# Sensor.net
KiCad netlist of a schematic drawn in Altium Designer
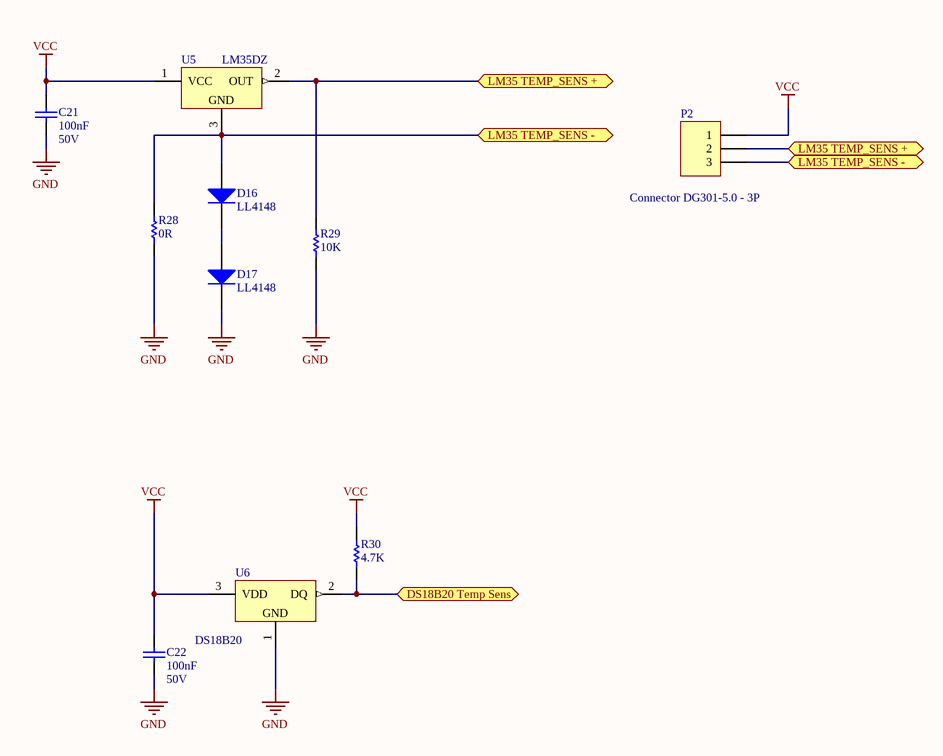
[diagram p0: Sensor.SchDoc]

(export (version "E")
  (design (tool "Eeschema 10.0.6"))
  (components
    (comp (ref "C21")
      (value "100nF")
      (footprint "3-0603_L")
      (description "Capacitor")
      (fields
        (field (name "VOLTAGE") "50V")
        (field (name "Comment") "Cap")
        (field (name "PUBLISHER") "Altium Limited")
      )
      (libsource (lib "Erdem_05112012") (part "Cap"))
    )
    (comp (ref "C22")
      (value "100nF")
      (footprint "3-0603_L")
      (description "Capacitor")
      (fields
        (field (name "VOLTAGE") "50V")
        (field (name "Comment") "Cap")
        (field (name "PUBLISHER") "Altium Limited")
      )
      (libsource (lib "Erdem_05112012") (part "Cap"))
    )
    (comp (ref "D16")
      (value "LL4148")
      (footprint "DL-35 - S")
      (description "1 Amp General Purpose Rectifier")
      (fields (field (name "PUBLISHER") "Altium Limited"))
      (libsource (lib "Erdem_05112012") (part "LL4148"))
    )
    (comp (ref "D17")
      (value "LL4148")
      (footprint "DL-35 - S")
      (description "1 Amp General Purpose Rectifier")
      (fields (field (name "PUBLISHER") "Altium Limited"))
      (libsource (lib "Erdem_05112012") (part "LL4148"))
    )
    (comp (ref "P2")
      (value "Connector DG301-5.0 - 3P")
      (footprint "Connector DG301-5.0 - 3P")
      (description "Connector, 3-Pin")
      (fields (field (name "PUBLISHER") "Altium Limited"))
      (libsource (lib "Erdem_05112012") (part "Connector DG301-5.0 - 3P"))
    )
    (comp (ref "R28")
      (value "0R")
      (footprint "8-1206")
      (description "Resistor")
      (fields (field (name "Comment") "Res1") (field (name "PUBLISHER") "Altium Limited"))
      (libsource (lib "Erdem_05112012") (part "Res1"))
    )
    (comp (ref "R29")
      (value "10K")
      (footprint "3-0603_L")
      (description "Resistor")
      (fields (field (name "Comment") "Res1") (field (name "PUBLISHER") "Altium Limited"))
      (libsource (lib "Erdem_05112012") (part "Res1"))
    )
    (comp (ref "R30")
      (value "4.7K")
      (footprint "3-0603_L")
      (description "Resistor")
      (fields (field (name "Comment") "Res1") (field (name "PUBLISHER") "Altium Limited"))
      (libsource (lib "Erdem_05112012") (part "Res1"))
    )
    (comp (ref "U5")
      (value "LM35DZ")
      (footprint "TO-92 Big")
      (description "Temperature Sensor")
      (fields (field (name "PUBLISHER") "Altium Limited"))
      (libsource (lib "Erdem_05112012") (part "LM35DZ"))
    )
    (comp (ref "U6")
      (value "DS18B20")
      (footprint "TO-92 Big")
      (description "1-Wire Temperature Sensor")
      (fields (field (name "PUBLISHER") "Altium Limited"))
      (libsource (lib "Erdem_05112012") (part "DS18B20"))
    )
  )
  (nets
    (net (code "1") (name "/DS18B20 Temp Sens") (class "Default")
      (node (ref "R30") (pin "1") (pinfunction "1_1") (pintype "passive"))
      (node (ref "U6") (pin "2") (pinfunction "DQ_2") (pintype "output"))
    )
    (net (code "2") (name "/LM35 TEMP_SENS +") (class "Default")
      (node (ref "P2") (pin "2") (pinfunction "2_2") (pintype "passive"))
      (node (ref "R29") (pin "2") (pinfunction "2_2") (pintype "passive"))
      (node (ref "U5") (pin "2") (pinfunction "OUT_2") (pintype "output"))
    )
    (net (code "3") (name "/LM35 TEMP_SENS -") (class "Default")
      (node (ref "D16") (pin "1") (pinfunction "A_1") (pintype "passive"))
      (node (ref "P2") (pin "3") (pinfunction "3_3") (pintype "passive"))
      (node (ref "R28") (pin "2") (pinfunction "2_2") (pintype "passive"))
      (node (ref "U5") (pin "3") (pinfunction "GND_3") (pintype "power_in"))
    )
    (net (code "4") (name "GND") (class "Default")
      (node (ref "C21") (pin "1") (pinfunction "1_1") (pintype "passive"))
      (node (ref "C22") (pin "1") (pinfunction "1_1") (pintype "passive"))
      (node (ref "D17") (pin "2") (pinfunction "K_2") (pintype "passive"))
      (node (ref "R28") (pin "1") (pinfunction "1_1") (pintype "passive"))
      (node (ref "R29") (pin "1") (pinfunction "1_1") (pintype "passive"))
      (node (ref "U6") (pin "1") (pinfunction "GND_1") (pintype "power_in"))
    )
    (net (code "5") (name "Net-(D16-K)") (class "Default")
      (node (ref "D16") (pin "2") (pinfunction "K_2") (pintype "passive"))
      (node (ref "D17") (pin "1") (pinfunction "A_1") (pintype "passive"))
    )
    (net (code "6") (name "VCC") (class "Default")
      (node (ref "C21") (pin "2") (pinfunction "2_2") (pintype "passive"))
      (node (ref "C22") (pin "2") (pinfunction "2_2") (pintype "passive"))
      (node (ref "P2") (pin "1") (pinfunction "1_1") (pintype "passive"))
      (node (ref "R30") (pin "2") (pinfunction "2_2") (pintype "passive"))
      (node (ref "U5") (pin "1") (pinfunction "VCC_1") (pintype "power_in"))
      (node (ref "U6") (pin "3") (pinfunction "VDD_3") (pintype "power_in"))
    )
  )
)
